# mcu.net
KiCad netlist of a schematic drawn in Altium Designer
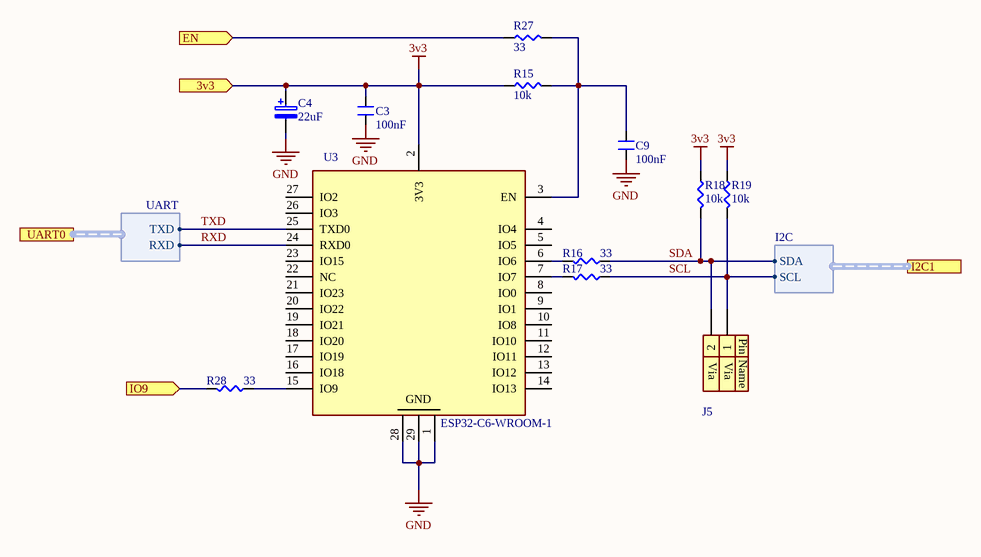
[diagram p0: mcu.SchDoc]

(export (version "E")
  (design (tool "Eeschema 10.0.6"))
  (components
    (comp (ref "C3")
      (value "100nF")
      (footprint "CAP0603")
      (description "Tolerance ±10%\nRated Voltage 50Vdc\nTemperature 0±30ppm/℃")
      (fields (field (name "PART NUMBER") "GCM188R71H104KA57J") (field (name "TOLERANCE") "10%"))
      (libsource (lib "Lib_Kam") (part "Capacitor"))
    )
    (comp (ref "C4")
      (value "22uF")
      (footprint "CAP TANT B")
      (fields
        (field (name "PART NUMBER") "TAJB226K016RNJ")
        (field (name "TOLERANCE") "10%")
        (field (name "MANUFACTURER") "KYOCERA AVX")
      )
      (libsource (lib "Lib_Kam") (part "Capacitor_polar_tantalum"))
    )
    (comp (ref "C9")
      (value "100nF")
      (footprint "CAP0603")
      (description "Tolerance ±10%\nRated Voltage 50Vdc\nTemperature 0±30ppm/℃")
      (fields (field (name "PART NUMBER") "GCM188R71H104KA57J") (field (name "TOLERANCE") "10%"))
      (libsource (lib "Lib_Kam") (part "Capacitor"))
    )
    (comp (ref "J5")
      (value "M20-9990246")
      (footprint "FP-M20-9990246-MFG")
      (description "CONN HEADER VERT 2POS 2.54MM")
      (fields (field (name "MANUFACTURER") "Harwin"))
      (libsource (lib "Lib_Kam") (part "CMP-15831-000009-1"))
    )
    (comp (ref "R15")
      (value "10k")
      (footprint "RES0603")
      (description "Tolerance ±1%\nPower (Watts) 0.1W, 1/10W\nTemperature Coefficient ±100ppm/°C")
      (fields (field (name "PART NUMBER") "CR0603-FX-1002ELF") (field (name "TOLERANCE") "1%"))
      (libsource (lib "Lib_Kam") (part "Resistor"))
    )
    (comp (ref "R16")
      (value "33")
      (footprint "RES0603")
      (description "Tolerance ±1%\nPower (Watts) 0.1W, 1/10W\nTemperature Coefficient ±100ppm/°C")
      (fields (field (name "PART NUMBER") "CR0603FX-33R0ELF") (field (name "TOLERANCE") "1%"))
      (libsource (lib "Lib_Kam") (part "Resistor"))
    )
    (comp (ref "R17")
      (value "33")
      (footprint "RES0603")
      (description "Tolerance ±1%\nPower (Watts) 0.1W, 1/10W\nTemperature Coefficient ±100ppm/°C")
      (fields (field (name "PART NUMBER") "CR0603FX-33R0ELF") (field (name "TOLERANCE") "1%"))
      (libsource (lib "Lib_Kam") (part "Resistor"))
    )
    (comp (ref "R18")
      (value "10k")
      (footprint "RES0603")
      (description "Tolerance ±1%\nPower (Watts) 0.1W, 1/10W\nTemperature Coefficient ±100ppm/°C")
      (fields (field (name "PART NUMBER") "CR0603-FX-1002ELF") (field (name "TOLERANCE") "1%"))
      (libsource (lib "Lib_Kam") (part "Resistor"))
    )
    (comp (ref "R19")
      (value "10k")
      (footprint "RES0603")
      (description "Tolerance ±1%\nPower (Watts) 0.1W, 1/10W\nTemperature Coefficient ±100ppm/°C")
      (fields (field (name "PART NUMBER") "CR0603-FX-1002ELF") (field (name "TOLERANCE") "1%"))
      (libsource (lib "Lib_Kam") (part "Resistor"))
    )
    (comp (ref "R27")
      (value "33")
      (footprint "RES0603")
      (description "Tolerance ±1%\nPower (Watts) 0.1W, 1/10W\nTemperature Coefficient ±100ppm/°C")
      (fields (field (name "PART NUMBER") "CR0603FX-33R0ELF") (field (name "TOLERANCE") "1%"))
      (libsource (lib "Lib_Kam") (part "Resistor"))
    )
    (comp (ref "R28")
      (value "33")
      (footprint "RES0603")
      (description "Tolerance ±1%\nPower (Watts) 0.1W, 1/10W\nTemperature Coefficient ±100ppm/°C")
      (fields (field (name "PART NUMBER") "CR0603FX-33R0ELF") (field (name "TOLERANCE") "1%"))
      (libsource (lib "Lib_Kam") (part "Resistor"))
    )
    (comp (ref "U3")
      (value "ESP32-C6-WROOM-1")
      (footprint "ESP32-C6-WROOM-1")
      (fields (field (name "MANUFACTURER") "Espressif Systems"))
      (libsource (lib "Lib_Kam") (part "ESP32-C6-WROOM-1"))
    )
  )
  (nets
    (net (code "3") (name "/EN") (class "Default") (node (ref "R27") (pin "2") (pintype "passive")))
    (net (code "4") (name "/IO9") (class "Default") (node (ref "R28") (pin "1") (pintype "passive")))
    (net (code "5") (name "/RXD") (class "Default")
      (node (ref "U3") (pin "24") (pinfunction "RXD0_24") (pintype "passive"))
    )
    (net (code "6") (name "/SCL") (class "Default")
      (node (ref "J5") (pin "1") (pinfunction "1_1") (pintype "passive"))
      (node (ref "R17") (pin "2") (pintype "passive"))
      (node (ref "R19") (pin "1") (pintype "passive"))
    )
    (net (code "7") (name "/SDA") (class "Default")
      (node (ref "J5") (pin "2") (pinfunction "2_2") (pintype "passive"))
      (node (ref "R16") (pin "2") (pintype "passive"))
      (node (ref "R18") (pin "1") (pintype "passive"))
    )
    (net (code "8") (name "/TXD") (class "Default")
      (node (ref "U3") (pin "25") (pinfunction "TXD0_25") (pintype "passive"))
    )
    (net (code "11") (name "3v3") (class "Default")
      (node (ref "C3") (pin "2") (pinfunction "2_2") (pintype "passive"))
      (node (ref "C4") (pin "1") (pinfunction "1_1") (pintype "passive"))
      (node (ref "R15") (pin "2") (pintype "passive"))
      (node (ref "R18") (pin "2") (pintype "passive"))
      (node (ref "R19") (pin "2") (pintype "passive"))
      (node (ref "U3") (pin "2") (pinfunction "3V3_2") (pintype "passive"))
    )
    (net (code "12") (name "GND") (class "Default")
      (node (ref "C3") (pin "1") (pinfunction "2_1") (pintype "passive"))
      (node (ref "C4") (pin "2") (pinfunction "2_2") (pintype "passive"))
      (node (ref "C9") (pin "1") (pinfunction "2_1") (pintype "passive"))
      (node (ref "U3") (pin "1") (pinfunction "GND_1") (pintype "passive"))
      (node (ref "U3") (pin "28") (pinfunction "GND_28") (pintype "passive"))
      (node (ref "U3") (pin "29") (pinfunction "GND_29") (pintype "passive"))
    )
    (net (code "13") (name "Net-(U3-EN)") (class "Default")
      (node (ref "C9") (pin "2") (pinfunction "2_2") (pintype "passive"))
      (node (ref "R15") (pin "1") (pintype "passive"))
      (node (ref "R27") (pin "1") (pintype "passive"))
      (node (ref "U3") (pin "3") (pinfunction "EN_3") (pintype "passive"))
    )
    (net (code "14") (name "Net-(U3-IO6)") (class "Default")
      (node (ref "R16") (pin "1") (pintype "passive"))
      (node (ref "U3") (pin "6") (pinfunction "IO6_6") (pintype "passive"))
    )
    (net (code "15") (name "Net-(U3-IO7)") (class "Default")
      (node (ref "R17") (pin "1") (pintype "passive"))
      (node (ref "U3") (pin "7") (pinfunction "IO7_7") (pintype "passive"))
    )
    (net (code "16") (name "Net-(U3-IO9)") (class "Default")
      (node (ref "R28") (pin "2") (pintype "passive"))
      (node (ref "U3") (pin "15") (pinfunction "IO9_15") (pintype "passive"))
    )
    (net (code "17") (name "unconnected-(U3-IO0-Pad8)") (class "Default")
      (node (ref "U3") (pin "8") (pinfunction "IO0_8") (pintype "passive"))
    )
    (net (code "18") (name "unconnected-(U3-IO1-Pad9)") (class "Default")
      (node (ref "U3") (pin "9") (pinfunction "IO1_9") (pintype "passive"))
    )
    (net (code "19") (name "unconnected-(U3-IO2-Pad27)") (class "Default")
      (node (ref "U3") (pin "27") (pinfunction "IO2_27") (pintype "passive"))
    )
    (net (code "20") (name "unconnected-(U3-IO3-Pad26)") (class "Default")
      (node (ref "U3") (pin "26") (pinfunction "IO3_26") (pintype "passive"))
    )
    (net (code "21") (name "unconnected-(U3-IO4-Pad4)") (class "Default")
      (node (ref "U3") (pin "4") (pinfunction "IO4_4") (pintype "passive"))
    )
    (net (code "22") (name "unconnected-(U3-IO5-Pad5)") (class "Default")
      (node (ref "U3") (pin "5") (pinfunction "IO5_5") (pintype "passive"))
    )
    (net (code "23") (name "unconnected-(U3-IO8-Pad10)") (class "Default")
      (node (ref "U3") (pin "10") (pinfunction "IO8_10") (pintype "passive"))
    )
    (net (code "24") (name "unconnected-(U3-IO10-Pad11)") (class "Default")
      (node (ref "U3") (pin "11") (pinfunction "IO10_11") (pintype "passive"))
    )
    (net (code "25") (name "unconnected-(U3-IO11-Pad12)") (class "Default")
      (node (ref "U3") (pin "12") (pinfunction "IO11_12") (pintype "passive"))
    )
    (net (code "26") (name "unconnected-(U3-IO12-Pad13)") (class "Default")
      (node (ref "U3") (pin "13") (pinfunction "IO12_13") (pintype "passive"))
    )
    (net (code "27") (name "unconnected-(U3-IO13-Pad14)") (class "Default")
      (node (ref "U3") (pin "14") (pinfunction "IO13_14") (pintype "passive"))
    )
    (net (code "28") (name "unconnected-(U3-IO15-Pad23)") (class "Default")
      (node (ref "U3") (pin "23") (pinfunction "IO15_23") (pintype "passive"))
    )
    (net (code "29") (name "unconnected-(U3-IO18-Pad16)") (class "Default")
      (node (ref "U3") (pin "16") (pinfunction "IO18_16") (pintype "passive"))
    )
    (net (code "30") (name "unconnected-(U3-IO19-Pad17)") (class "Default")
      (node (ref "U3") (pin "17") (pinfunction "IO19_17") (pintype "passive"))
    )
    (net (code "31") (name "unconnected-(U3-IO20-Pad18)") (class "Default")
      (node (ref "U3") (pin "18") (pinfunction "IO20_18") (pintype "passive"))
    )
    (net (code "32") (name "unconnected-(U3-IO21-Pad19)") (class "Default")
      (node (ref "U3") (pin "19") (pinfunction "IO21_19") (pintype "passive"))
    )
    (net (code "33") (name "unconnected-(U3-IO22-Pad20)") (class "Default")
      (node (ref "U3") (pin "20") (pinfunction "IO22_20") (pintype "passive"))
    )
    (net (code "34") (name "unconnected-(U3-IO23-Pad21)") (class "Default")
      (node (ref "U3") (pin "21") (pinfunction "IO23_21") (pintype "passive"))
    )
    (net (code "35") (name "unconnected-(U3-NC-Pad22)") (class "Default")
      (node (ref "U3") (pin "22") (pinfunction "NC_22") (pintype "passive"))
    )
  )
)
